# LIS331DLTR_-_MEMS_Motion_Sensor_-_Accele.net
KiCad netlist of a schematic drawn in Altium Designer
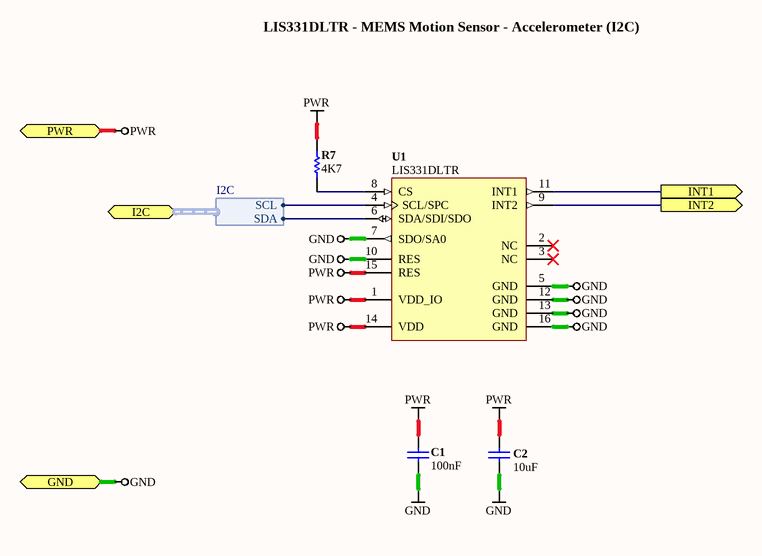
[diagram p0: LIS331DLTR - MEMS Motion Sensor - Accelerometer (I2C).SchDoc]

(export (version "E")
  (design (tool "Eeschema 10.0.6"))
  (components
    (comp (ref "C1")
      (value "100nF")
      (footprint "CAPC0402(1005)60_L")
      (description "CAP 100nF 10V ±10% 0402 (1005 Metric) Thickness 0.6mm SMD")
      (fields (field (name "TOLERANCE") "±10%") (field (name "Comment") "CAP 100nF 10V 0402(1005)"))
      (libsource (lib "Altium Vault") (part "CMP-1034-02065-1"))
    )
    (comp (ref "C2")
      (value "10uF")
      (footprint "CAPC0603(1608)100_L")
      (description "CAP 10uF 10V ±10% 0603 (1608 Metric) Thickness 1mm SMD")
      (fields (field (name "TOLERANCE") "±10%") (field (name "Comment") "CAP 10uF 10V 0603(1608)"))
      (libsource (lib "Altium Vault") (part "CMP-1035-02799-1"))
    )
    (comp (ref "R7")
      (value "4K7")
      (footprint "RESC0402(1005)40_L")
      (fields (field (name "POWER") "1/16 W"))
      (libsource (lib "Component_Database") (part "RES"))
    )
    (comp (ref "U1")
      (value "LIS331DLTR")
      (footprint "LGA16-3X3X1_L")
      (fields (field (name "MANUFACTURER") "STMicroelectronics"))
      (libsource (lib "Altium Content Vault") (part "CMP-0234-00061-2"))
    )
  )
  (nets
    (net (code "2") (name "/INT1") (class "Default")
      (node (ref "U1") (pin "11") (pinfunction "INT1_11") (pintype "output"))
    )
    (net (code "3") (name "/INT2") (class "Default")
      (node (ref "U1") (pin "9") (pinfunction "INT2_9") (pintype "output"))
    )
    (net (code "4") (name "/SCL") (class "Default")
      (node (ref "U1") (pin "4") (pinfunction "SCL/SPC_4") (pintype "input"))
    )
    (net (code "5") (name "/SDA") (class "Default")
      (node (ref "U1") (pin "6") (pinfunction "SDA/SDI/SDO_6") (pintype "bidirectional"))
    )
    (net (code "7") (name "GND") (class "Default")
      (node (ref "C1") (pin "2") (pinfunction "2_2") (pintype "passive"))
      (node (ref "C2") (pin "2") (pinfunction "2_2") (pintype "passive"))
      (node (ref "U1") (pin "10") (pinfunction "RES_10") (pintype "passive"))
      (node (ref "U1") (pin "12") (pinfunction "GND_12") (pintype "power_in"))
      (node (ref "U1") (pin "13") (pinfunction "GND_13") (pintype "power_in"))
      (node (ref "U1") (pin "16") (pinfunction "GND_16") (pintype "power_in"))
      (node (ref "U1") (pin "5") (pinfunction "GND_5") (pintype "power_in"))
      (node (ref "U1") (pin "7") (pinfunction "SDO/SA0_7") (pintype "output"))
    )
    (net (code "8") (name "Net-(U1-CS)") (class "Default")
      (node (ref "R7") (pin "1") (pinfunction "1_1") (pintype "passive"))
      (node (ref "U1") (pin "8") (pinfunction "CS_8") (pintype "input"))
    )
    (net (code "9") (name "PWR") (class "Default")
      (node (ref "C1") (pin "1") (pinfunction "1_1") (pintype "passive"))
      (node (ref "C2") (pin "1") (pinfunction "1_1") (pintype "passive"))
      (node (ref "R7") (pin "2") (pinfunction "2_2") (pintype "passive"))
      (node (ref "U1") (pin "1") (pinfunction "VDD_IO_1") (pintype "power_in"))
      (node (ref "U1") (pin "14") (pinfunction "VDD_14") (pintype "power_in"))
      (node (ref "U1") (pin "15") (pinfunction "RES_15") (pintype "passive"))
    )
    (net (code "10") (name "unconnected-(U1-NC-Pad2)") (class "Default")
      (node (ref "U1") (pin "2") (pinfunction "NC_2") (pintype "passive+no_connect"))
    )
    (net (code "11") (name "unconnected-(U1-NC-Pad3)") (class "Default")
      (node (ref "U1") (pin "3") (pinfunction "NC_3") (pintype "passive+no_connect"))
    )
  )
)
